# CH32V303RBT6-R1.net
KiCad netlist of a schematic drawn in Altium Designer
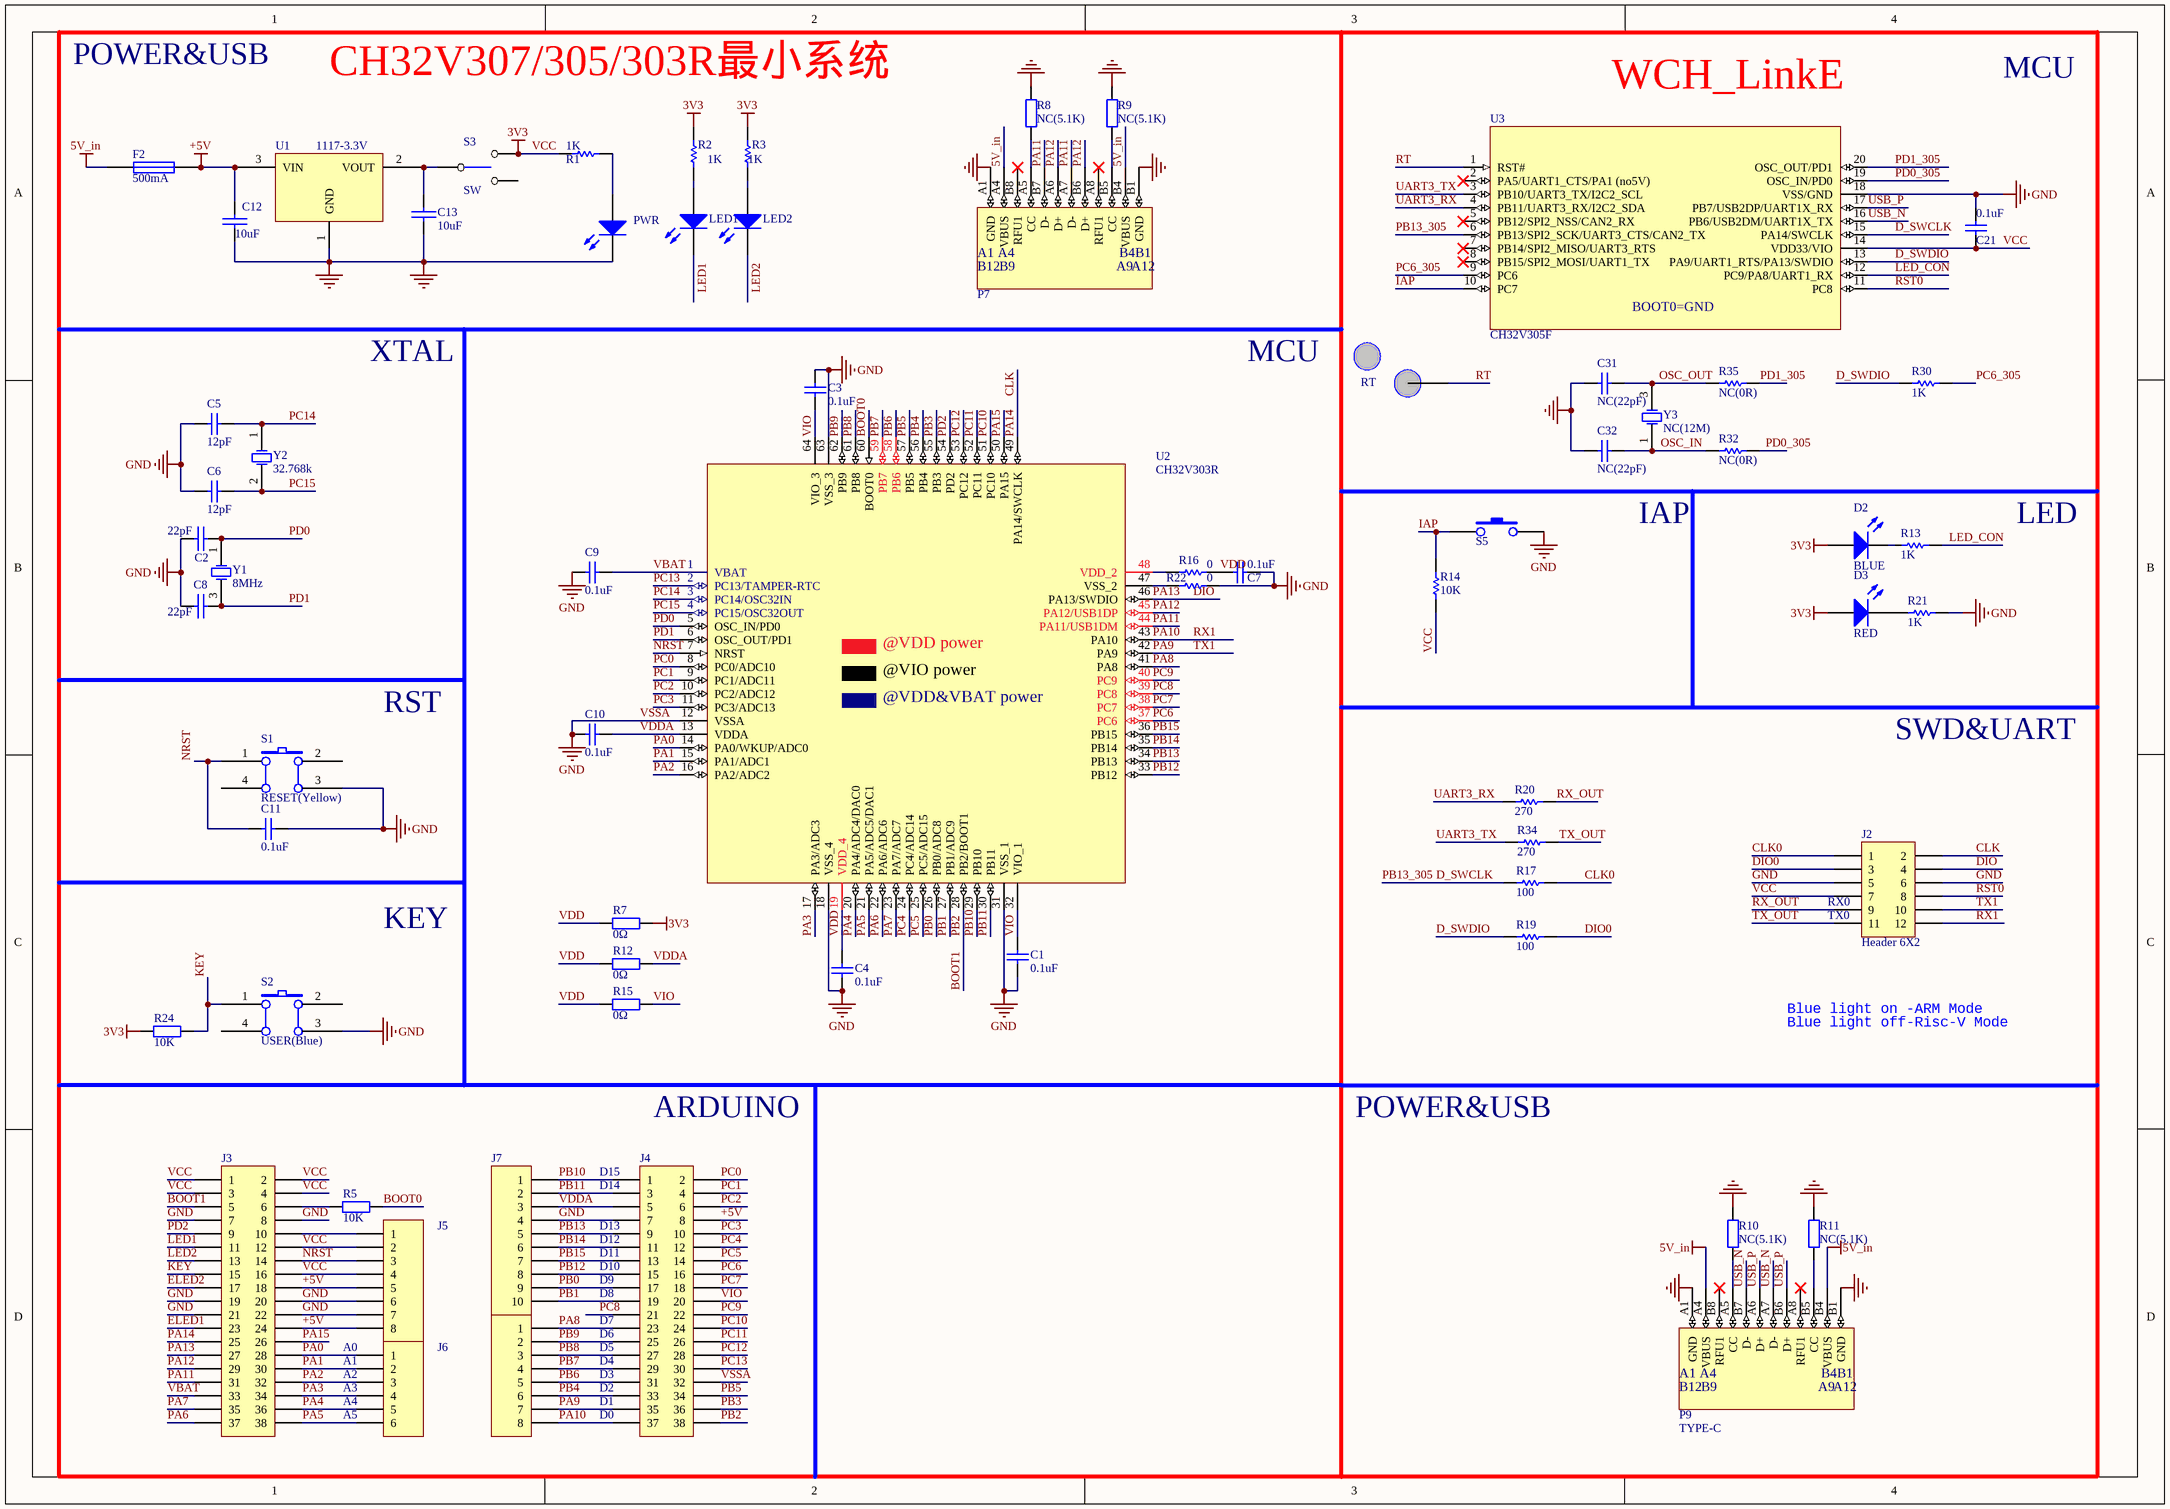
[diagram p0: CH32V303RBT6-R1.SchDoc]

(export (version "E")
  (design (tool "Eeschema 10.0.6"))
  (components
    (comp (ref "C1")
      (value "0.1uF")
      (footprint "0603_C")
      (description "Capacitor")
      (libsource (lib "Miscellaneous Devices") (part "Cap"))
    )
    (comp (ref "C2")
      (value "22pF")
      (footprint "0603_C")
      (description "Capacitor")
      (libsource (lib "*") (part "CAP"))
    )
    (comp (ref "C3")
      (value "0.1uF")
      (footprint "0603_C")
      (description "Capacitor")
      (libsource (lib "Miscellaneous Devices") (part "Cap"))
    )
    (comp (ref "C4")
      (value "0.1uF")
      (footprint "0603_C")
      (description "Capacitor")
      (libsource (lib "Miscellaneous Devices") (part "Cap"))
    )
    (comp (ref "C5")
      (value "12pF")
      (footprint "0603_C")
      (description "Capacitor")
      (libsource (lib "Miscellaneous Devices") (part "Cap"))
    )
    (comp (ref "C6")
      (value "12pF")
      (footprint "0603_C")
      (description "Capacitor")
      (libsource (lib "Miscellaneous Devices") (part "Cap"))
    )
    (comp (ref "C7")
      (value "0.1uF")
      (footprint "0603_C")
      (description "Capacitor")
      (libsource (lib "Miscellaneous Devices") (part "Cap"))
    )
    (comp (ref "C8")
      (value "22pF")
      (footprint "0603_C")
      (description "Capacitor")
      (libsource (lib "*") (part "CAP"))
    )
    (comp (ref "C9")
      (value "0.1uF")
      (footprint "0603_C")
      (description "Capacitor")
      (libsource (lib "Miscellaneous Devices") (part "Cap"))
    )
    (comp (ref "C10")
      (value "0.1uF")
      (footprint "0603_C")
      (description "Capacitor")
      (libsource (lib "Miscellaneous Devices") (part "Cap"))
    )
    (comp (ref "C11")
      (value "0.1uF")
      (footprint "0603_C")
      (description "Capacitor")
      (libsource (lib "Miscellaneous Devices") (part "Cap"))
    )
    (comp (ref "C12")
      (value "10uF")
      (footprint "3216_C")
      (description "Capacitor")
      (libsource (lib "*") (part "CAP"))
    )
    (comp (ref "C13")
      (value "10uF")
      (footprint "3216_C")
      (description "Capacitor")
      (libsource (lib "*") (part "CAP"))
    )
    (comp (ref "C21")
      (value "0.1uF")
      (footprint "0603_C")
      (description "Capacitor")
      (libsource (lib "Miscellaneous Devices") (part "Cap"))
    )
    (comp (ref "C31")
      (value "NC(22pF)")
      (footprint "0603_C")
      (description "Capacitor")
      (fields (field (name "PUBLISHER") "Altium Limited"))
      (libsource (lib "*") (part "Cap"))
    )
    (comp (ref "C32")
      (value "NC(22pF)")
      (footprint "0603_C")
      (description "Capacitor")
      (fields (field (name "PUBLISHER") "Altium Limited"))
      (libsource (lib "*") (part "Cap"))
    )
    (comp (ref "D2")
      (value "BLUE")
      (footprint "0603+")
      (description "Typical RED, GREEN, YELLOW, AMBER GaAs LED")
      (fields (field (name "PUBLISHER") "Altium Limited"))
      (libsource (lib "MYLIB") (part "D0603"))
    )
    (comp (ref "D3")
      (value "RED")
      (footprint "0603+")
      (description "Typical RED, GREEN, YELLOW, AMBER GaAs LED")
      (fields (field (name "PUBLISHER") "Altium Limited"))
      (libsource (lib "MYLIB") (part "D0603"))
    )
    (comp (ref "F2")
      (value "500mA")
      (footprint "0805")
      (description "Fuse")
      (libsource (lib "*") (part "FUSE1"))
    )
    (comp (ref "J2")
      (value "Header 6X2")
      (footprint "IDC12-2.54mm")
      (description "Header, 6-Pin, Dual row")
      (fields (field (name "PUBLISHER") "Altium Limited"))
      (libsource (lib "Miscellaneous Connectors") (part "Header 6X2"))
    )
    (comp (ref "J3")
      (value "Header 19X2")
      (footprint "IDC38-2.54mm")
      (description "Header, 19-Pin, Dual row")
      (fields (field (name "PUBLISHER") "Altium Limited"))
      (libsource (lib "Miscellaneous Connectors") (part "Header 19X2"))
    )
    (comp (ref "J4")
      (value "Header 19X2")
      (footprint "IDC38-2.54mm")
      (description "Header, 19-Pin, Dual row")
      (fields (field (name "PUBLISHER") "Altium Limited"))
      (libsource (lib "Miscellaneous Connectors") (part "Header 19X2"))
    )
    (comp (ref "J5")
      (value "Header 8")
      (footprint "SIP8-2.54mm")
      (description "Header, 8-Pin")
      (fields (field (name "PUBLISHER") "Altium Limited"))
      (libsource (lib "") (part "Header 8_1"))
    )
    (comp (ref "J6")
      (value "Header 6")
      (footprint "SIP6-2.54MM")
      (description "Header, 6-Pin")
      (fields (field (name "PUBLISHER") "Altium Limited"))
      (libsource (lib "Miscellaneous Connectors") (part "Header 6"))
    )
    (comp (ref "J7")
      (value "Header 10")
      (footprint "SIP10-2.54mm")
      (description "Header, 10-Pin")
      (fields (field (name "PUBLISHER") "Altium Limited"))
      (libsource (lib "Miscellaneous Connectors") (part "Header 10"))
    )
    (comp (ref "J8")
      (value "Header 8")
      (footprint "SIP8-2.54mm")
      (description "Header, 8-Pin")
      (fields (field (name "PUBLISHER") "Altium Limited"))
      (libsource (lib "Miscellaneous Connectors") (part "Header 8"))
    )
    (comp (ref "LED1")
      (value "LED1   blue")
      (footprint "0603+")
      (description "Typical INFRARED GaAs LED")
      (fields (field (name "PUBLISHER") "Altium Limited"))
      (libsource (lib "Miscellaneous Devices") (part "LED0"))
    )
    (comp (ref "LED2")
      (value "LED2  blue")
      (footprint "0603+")
      (description "Typical INFRARED GaAs LED")
      (fields (field (name "PUBLISHER") "Altium Limited"))
      (libsource (lib "Miscellaneous Devices") (part "LED0"))
    )
    (comp (ref "P7")
      (value "TYPE-C")
      (footprint "TYPE-C-Receptacle-2.0")
      (libsource (lib "*") (part "TYPE-C1"))
    )
    (comp (ref "P9")
      (value "TYPE-C")
      (footprint "TYPE-C-Receptacle-2.0")
      (libsource (lib "*") (part "TYPE-C1"))
    )
    (comp (ref "PWR")
      (value "POWER  red")
      (footprint "0603+")
      (description "Typical INFRARED GaAs LED")
      (fields (field (name "PUBLISHER") "Altium Limited"))
      (libsource (lib "Miscellaneous Devices") (part "LED0"))
    )
    (comp (ref "R1")
      (value "1K")
      (footprint "0603")
      (description "Semiconductor Resistor")
      (libsource (lib "Miscellaneous Devices") (part "Res Semi"))
    )
    (comp (ref "R2")
      (value "1K")
      (footprint "0603")
      (description "Semiconductor Resistor")
      (libsource (lib "Miscellaneous Devices") (part "Res Semi"))
    )
    (comp (ref "R3")
      (value "1K")
      (footprint "0603")
      (description "Semiconductor Resistor")
      (libsource (lib "Miscellaneous Devices") (part "Res Semi"))
    )
    (comp (ref "R5")
      (value "10K")
      (footprint "0603")
      (description "Resistor")
      (libsource (lib "") (part "Res2_1"))
    )
    (comp (ref "R7")
      (value "0Ω")
      (footprint "0603")
      (description "Resistor")
      (libsource (lib "Miscellaneous Devices") (part "Res2"))
    )
    (comp (ref "R8")
      (value "NC(5.1K)")
      (footprint "0603")
      (description "Resistor")
      (libsource (lib "") (part "Res2_3"))
    )
    (comp (ref "R9")
      (value "NC(5.1K)")
      (footprint "0603")
      (description "Resistor")
      (libsource (lib "") (part "Res2_3"))
    )
    (comp (ref "R10")
      (value "NC(5.1K)")
      (footprint "0603")
      (description "Resistor")
      (libsource (lib "") (part "Res2_2"))
    )
    (comp (ref "R11")
      (value "NC(5.1K)")
      (footprint "0603")
      (description "Resistor")
      (libsource (lib "") (part "Res2_2"))
    )
    (comp (ref "R12")
      (value "0Ω")
      (footprint "0603")
      (description "Resistor")
      (libsource (lib "Miscellaneous Devices") (part "Res2"))
    )
    (comp (ref "R13")
      (value "1K")
      (footprint "0603")
      (description "Resistor")
      (fields (field (name "PUBLISHER") "Altium Limited"))
      (libsource (lib "MYLIB") (part "0603-1"))
    )
    (comp (ref "R14")
      (value "10K")
      (footprint "0603")
      (description "Resistor")
      (fields (field (name "PUBLISHER") "Altium Limited"))
      (libsource (lib "MYLIB") (part "0603-1"))
    )
    (comp (ref "R15")
      (value "0Ω")
      (footprint "0603")
      (description "Resistor")
      (libsource (lib "Miscellaneous Devices") (part "Res2"))
    )
    (comp (ref "R16")
      (value "0")
      (footprint "0603")
      (description "Resistor")
      (fields (field (name "PUBLISHER") "Altium Limited"))
      (libsource (lib "MYLIB") (part "0603-1"))
    )
    (comp (ref "R17")
      (value "100")
      (footprint "0603")
      (description "Resistor")
      (fields (field (name "PUBLISHER") "Altium Limited"))
      (libsource (lib "MYLIB") (part "0603-1"))
    )
    (comp (ref "R19")
      (value "100")
      (footprint "0603")
      (description "Resistor")
      (fields (field (name "PUBLISHER") "Altium Limited"))
      (libsource (lib "MYLIB") (part "0603-1"))
    )
    (comp (ref "R20")
      (value "270")
      (footprint "0603")
      (description "Resistor")
      (fields (field (name "PUBLISHER") "Altium Limited"))
      (libsource (lib "MYLIB") (part "0603-1"))
    )
    (comp (ref "R21")
      (value "1K")
      (footprint "0603")
      (description "Resistor")
      (fields (field (name "PUBLISHER") "Altium Limited"))
      (libsource (lib "MYLIB") (part "0603-1"))
    )
    (comp (ref "R22")
      (value "0")
      (footprint "0603")
      (description "Resistor")
      (fields (field (name "PUBLISHER") "Altium Limited"))
      (libsource (lib "MYLIB") (part "0603-1"))
    )
    (comp (ref "R24")
      (value "10K")
      (footprint "0603")
      (description "Resistor")
      (libsource (lib "Miscellaneous Devices") (part "Res2"))
    )
    (comp (ref "R30")
      (value "1K")
      (footprint "0603")
      (description "Resistor")
      (fields (field (name "PUBLISHER") "Altium Limited"))
      (libsource (lib "MYLIB") (part "0603-1"))
    )
    (comp (ref "R32")
      (value "NC(0R)")
      (footprint "0603")
      (description "Resistor")
      (fields (field (name "PUBLISHER") "Altium Limited"))
      (libsource (lib "MYLIB") (part "0603-1"))
    )
    (comp (ref "R34")
      (value "270")
      (footprint "0603")
      (description "Resistor")
      (fields (field (name "PUBLISHER") "Altium Limited"))
      (libsource (lib "MYLIB") (part "0603-1"))
    )
    (comp (ref "R35")
      (value "NC(0R)")
      (footprint "0603")
      (description "Resistor")
      (fields (field (name "PUBLISHER") "Altium Limited"))
      (libsource (lib "MYLIB") (part "0603-1"))
    )
    (comp (ref "RT")
      (value "Testpoint")
      (footprint "TESTPOINT1")
      (description "测试点")
      (libsource (lib "wch_sch_others") (part "Testpoint"))
    )
    (comp (ref "S1")
      (value "RESET(Yellow)")
      (footprint "KEYX")
      (description "SE PUSHBUTTON")
      (libsource (lib "Documents") (part "SW PUSHBUTTON"))
    )
    (comp (ref "S2")
      (value "USER(Blue)")
      (footprint "KEYX")
      (description "SE PUSHBUTTON")
      (libsource (lib "Documents") (part "SW PUSHBUTTON"))
    )
    (comp (ref "S3") (value "SW") (footprint "SW1") (libsource (lib "MYSCH") (part "SW")))
    (comp (ref "S5") (value "KEY") (footprint "贴片按键") (libsource (lib "*") (part "KEY")))
    (comp (ref "U1")
      (value "1117-3.3V")
      (footprint "SOT-223")
      (libsource (lib "wch_sch_others") (part "1117-3.3V"))
    )
    (comp (ref "U2")
      (value "CH32V303R")
      (footprint "LQFP64M_10x10")
      (description "RISC-V FPU HD-MCU, 144MHz, 8*UART, 10*Timer, 4*OPA")
      (libsource (lib "CHXXX") (part "CH32V303R"))
    )
    (comp (ref "U3")
      (value "CH32V305F")
      (footprint "TSSOP20")
      (description "RISC-V FPU HD-MCU, 144MHz, USB_480M, CAN, UART*2, SPI")
      (libsource (lib "CHXXX") (part "CH32V305F"))
    )
    (comp (ref "Y1")
      (value "8MHz")
      (footprint "XT3225")
      (description "Crystal Oscillator")
      (fields (field (name "PUBLISHER") "Altium Limited"))
      (libsource (lib "*") (part "XTAL"))
    )
    (comp (ref "Y2")
      (value "32.768k")
      (footprint "FC-135")
      (description "Crystal Oscillator")
      (fields (field (name "PUBLISHER") "Altium Limited"))
      (libsource (lib "Miscellaneous Devices") (part "XTAL"))
    )
    (comp (ref "Y3")
      (value "NC(12M)")
      (footprint "XT3225")
      (description "Crystal Oscillator")
      (libsource (lib "*") (part "XTAL"))
    )
  )
  (nets
    (net (code "1") (name "+5V") (class "Default")
      (node (ref "C12") (pin "1") (pinfunction "1_1") (pintype "passive"))
      (node (ref "F2") (pin "2") (pinfunction "2_2") (pintype "passive"))
      (node (ref "J3") (pin "18") (pinfunction "18_18") (pintype "passive"))
      (node (ref "J3") (pin "24") (pinfunction "24_24") (pintype "passive"))
      (node (ref "J4") (pin "8") (pinfunction "8_8") (pintype "passive"))
      (node (ref "J5") (pin "5") (pinfunction "5_5") (pintype "passive"))
      (node (ref "J5") (pin "8") (pinfunction "8_8") (pintype "passive"))
      (node (ref "U1") (pin "3") (pinfunction "VIN_3") (pintype "passive"))
    )
    (net (code "2") (name "/BOOT0") (class "Default")
      (node (ref "R5") (pin "2") (pinfunction "2_2") (pintype "passive"))
      (node (ref "U2") (pin "60") (pinfunction "BOOT0_60") (pintype "input"))
    )
    (net (code "3") (name "/BOOT1") (class "Default")
      (node (ref "J3") (pin "5") (pinfunction "5_5") (pintype "passive"))
      (node (ref "J4") (pin "38") (pinfunction "38_38") (pintype "passive"))
      (node (ref "U2") (pin "28") (pinfunction "PB2/BOOT1_28") (pintype "bidirectional"))
    )
    (net (code "4") (name "/CLK") (class "Default")
      (node (ref "J2") (pin "2") (pinfunction "2_2") (pintype "passive"))
      (node (ref "J3") (pin "25") (pinfunction "25_25") (pintype "passive"))
      (node (ref "U2") (pin "49") (pinfunction "PA14/SWCLK_49") (pintype "bidirectional"))
    )
    (net (code "5") (name "/CLK0") (class "Default")
      (node (ref "J2") (pin "1") (pinfunction "1_1") (pintype "passive"))
      (node (ref "R17") (pin "1") (pinfunction "1_1") (pintype "passive"))
    )
    (net (code "6") (name "/DIO") (class "Default")
      (node (ref "J2") (pin "4") (pinfunction "4_4") (pintype "passive"))
      (node (ref "J3") (pin "27") (pinfunction "27_27") (pintype "passive"))
      (node (ref "U2") (pin "46") (pinfunction "PA13/SWDIO_46") (pintype "bidirectional"))
    )
    (net (code "7") (name "/DIO0") (class "Default")
      (node (ref "J2") (pin "3") (pinfunction "3_3") (pintype "passive"))
      (node (ref "R19") (pin "1") (pinfunction "1_1") (pintype "passive"))
    )
    (net (code "8") (name "/D_SWCLK") (class "Default")
      (node (ref "R17") (pin "2") (pinfunction "2_2") (pintype "passive"))
      (node (ref "U3") (pin "15") (pinfunction "PA14/SWCLK_15") (pintype "bidirectional"))
      (node (ref "U3") (pin "6") (pinfunction "PB13/SPI2_SCK/UART3_CTS/CAN2_TX_6") (pintype "bidirectional"))
    )
    (net (code "9") (name "/D_SWDIO") (class "Default")
      (node (ref "R19") (pin "2") (pinfunction "2_2") (pintype "passive"))
      (node (ref "R30") (pin "1") (pinfunction "1_1") (pintype "passive"))
      (node (ref "U3") (pin "13") (pinfunction "PA9/UART1_RTS/PA13/SWDIO_13") (pintype "bidirectional"))
    )
    (net (code "10") (name "/ELED1") (class "Default")
      (node (ref "J3") (pin "23") (pinfunction "23_23") (pintype "passive"))
    )
    (net (code "11") (name "/ELED2") (class "Default")
      (node (ref "J3") (pin "17") (pinfunction "17_17") (pintype "passive"))
    )
    (net (code "12") (name "/IAP") (class "Default")
      (node (ref "R14") (pin "1") (pinfunction "1_1") (pintype "passive"))
      (node (ref "S5") (pin "1") (pinfunction "1_1") (pintype "passive"))
      (node (ref "U3") (pin "10") (pinfunction "PC7_10") (pintype "bidirectional"))
    )
    (net (code "13") (name "/KEY") (class "Default")
      (node (ref "J3") (pin "15") (pinfunction "15_15") (pintype "passive"))
      (node (ref "R24") (pin "1") (pinfunction "1_1") (pintype "passive"))
      (node (ref "S2") (pin "1") (pinfunction "A0_1") (pintype "passive"))
    )
    (net (code "14") (name "/LED1") (class "Default")
      (node (ref "J3") (pin "11") (pinfunction "11_11") (pintype "passive"))
      (node (ref "LED1") (pin "2") (pinfunction "K_2") (pintype "passive"))
    )
    (net (code "15") (name "/LED2") (class "Default")
      (node (ref "J3") (pin "13") (pinfunction "13_13") (pintype "passive"))
      (node (ref "LED2") (pin "2") (pinfunction "K_2") (pintype "passive"))
    )
    (net (code "16") (name "/LED_CON") (class "Default")
      (node (ref "R13") (pin "1") (pinfunction "1_1") (pintype "passive"))
      (node (ref "U3") (pin "12") (pinfunction "PC9/PA8/UART1_RX_12") (pintype "bidirectional"))
    )
    (net (code "17") (name "/NRST") (class "Default")
      (node (ref "C11") (pin "2") (pinfunction "2_2") (pintype "passive"))
      (node (ref "J3") (pin "14") (pinfunction "14_14") (pintype "passive"))
      (node (ref "J5") (pin "3") (pinfunction "3_3") (pintype "passive"))
      (node (ref "S1") (pin "1") (pinfunction "A0_1") (pintype "passive"))
      (node (ref "U2") (pin "7") (pinfunction "NRST_7") (pintype "input"))
    )
    (net (code "18") (name "/OSC_IN") (class "Default")
      (node (ref "C32") (pin "2") (pinfunction "2_2") (pintype "passive"))
      (node (ref "R32") (pin "2") (pinfunction "2_2") (pintype "passive"))
      (node (ref "Y3") (pin "1") (pinfunction "OSC1_1") (pintype "passive"))
    )
    (net (code "19") (name "/OSC_OUT") (class "Default")
      (node (ref "C31") (pin "2") (pinfunction "2_2") (pintype "passive"))
      (node (ref "R35") (pin "2") (pinfunction "2_2") (pintype "passive"))
      (node (ref "Y3") (pin "3") (pinfunction "OSC2_3") (pintype "passive"))
    )
    (net (code "20") (name "/PA0") (class "Default")
      (node (ref "J3") (pin "28") (pinfunction "28_28") (pintype "passive"))
      (node (ref "J6") (pin "1") (pinfunction "1_1") (pintype "passive"))
      (node (ref "U2") (pin "14") (pinfunction "PA0/WKUP/ADC0_14") (pintype "bidirectional"))
    )
    (net (code "21") (name "/PA1") (class "Default")
      (node (ref "J3") (pin "30") (pinfunction "30_30") (pintype "passive"))
      (node (ref "J6") (pin "2") (pinfunction "2_2") (pintype "passive"))
      (node (ref "U2") (pin "15") (pinfunction "PA1/ADC1_15") (pintype "bidirectional"))
    )
    (net (code "22") (name "/PA2") (class "Default")
      (node (ref "J3") (pin "32") (pinfunction "32_32") (pintype "passive"))
      (node (ref "J6") (pin "3") (pinfunction "3_3") (pintype "passive"))
      (node (ref "U2") (pin "16") (pinfunction "PA2/ADC2_16") (pintype "bidirectional"))
    )
    (net (code "23") (name "/PA3") (class "Default")
      (node (ref "J3") (pin "34") (pinfunction "34_34") (pintype "passive"))
      (node (ref "J6") (pin "4") (pinfunction "4_4") (pintype "passive"))
      (node (ref "U2") (pin "17") (pinfunction "PA3/ADC3_17") (pintype "bidirectional"))
    )
    (net (code "24") (name "/PA4") (class "Default")
      (node (ref "J3") (pin "36") (pinfunction "36_36") (pintype "passive"))
      (node (ref "J6") (pin "5") (pinfunction "5_5") (pintype "passive"))
      (node (ref "U2") (pin "20") (pinfunction "PA4/ADC4/DAC0_20") (pintype "bidirectional"))
    )
    (net (code "25") (name "/PA5") (class "Default")
      (node (ref "J3") (pin "38") (pinfunction "38_38") (pintype "passive"))
      (node (ref "J6") (pin "6") (pinfunction "6_6") (pintype "passive"))
      (node (ref "U2") (pin "21") (pinfunction "PA5/ADC5/DAC1_21") (pintype "bidirectional"))
    )
    (net (code "26") (name "/PA6") (class "Default")
      (node (ref "J3") (pin "37") (pinfunction "37_37") (pintype "passive"))
      (node (ref "U2") (pin "22") (pinfunction "PA6/ADC6_22") (pintype "bidirectional"))
    )
    (net (code "27") (name "/PA7") (class "Default")
      (node (ref "J3") (pin "35") (pinfunction "35_35") (pintype "passive"))
      (node (ref "U2") (pin "23") (pinfunction "PA7/ADC7_23") (pintype "bidirectional"))
    )
    (net (code "28") (name "/PA8") (class "Default")
      (node (ref "J4") (pin "23") (pinfunction "23_23") (pintype "passive"))
      (node (ref "J8") (pin "1") (pinfunction "1_1") (pintype "passive"))
      (node (ref "U2") (pin "41") (pinfunction "PA8_41") (pintype "bidirectional"))
    )
    (net (code "29") (name "/PA9") (class "Default")
      (node (ref "J2") (pin "10") (pinfunction "10_10") (pintype "passive"))
      (node (ref "J4") (pin "35") (pinfunction "35_35") (pintype "passive"))
      (node (ref "J8") (pin "7") (pinfunction "7_7") (pintype "passive"))
      (node (ref "U2") (pin "42") (pinfunction "PA9_42") (pintype "bidirectional"))
    )
    (net (code "30") (name "/PA10") (class "Default")
      (node (ref "J2") (pin "12") (pinfunction "12_12") (pintype "passive"))
      (node (ref "J4") (pin "37") (pinfunction "37_37") (pintype "passive"))
      (node (ref "J8") (pin "8") (pinfunction "8_8") (pintype "passive"))
      (node (ref "U2") (pin "43") (pinfunction "PA10_43") (pintype "bidirectional"))
    )
    (net (code "31") (name "/PA11") (class "Default")
      (node (ref "J3") (pin "31") (pinfunction "31_31") (pintype "passive"))
      (node (ref "P7") (pin "A7") (pinfunction "D-_A7") (pintype "bidirectional"))
      (node (ref "P7") (pin "B7") (pinfunction "D-_B7") (pintype "bidirectional"))
      (node (ref "U2") (pin "44") (pinfunction "PA11/USB1DM_44") (pintype "bidirectional"))
    )
    (net (code "32") (name "/PA12") (class "Default")
      (node (ref "J3") (pin "29") (pinfunction "29_29") (pintype "passive"))
      (node (ref "P7") (pin "A6") (pinfunction "D+_A6") (pintype "bidirectional"))
      (node (ref "P7") (pin "B6") (pinfunction "D+_B6") (pintype "bidirectional"))
      (node (ref "U2") (pin "45") (pinfunction "PA12/USB1DP_45") (pintype "bidirectional"))
    )
    (net (code "33") (name "/PA15") (class "Default")
      (node (ref "J3") (pin "26") (pinfunction "26_26") (pintype "passive"))
      (node (ref "U2") (pin "50") (pinfunction "PA15_50") (pintype "bidirectional"))
    )
    (net (code "34") (name "/PB0") (class "Default")
      (node (ref "J4") (pin "17") (pinfunction "17_17") (pintype "passive"))
      (node (ref "J7") (pin "9") (pinfunction "9_9") (pintype "passive"))
      (node (ref "U2") (pin "26") (pinfunction "PB0/ADC8_26") (pintype "bidirectional"))
    )
    (net (code "35") (name "/PB1") (class "Default")
      (node (ref "J4") (pin "19") (pinfunction "19_19") (pintype "passive"))
      (node (ref "J7") (pin "10") (pinfunction "10_10") (pintype "passive"))
      (node (ref "U2") (pin "27") (pinfunction "PB1/ADC9_27") (pintype "bidirectional"))
    )
    (net (code "36") (name "/PB3") (class "Default")
      (node (ref "J4") (pin "36") (pinfunction "36_36") (pintype "passive"))
      (node (ref "U2") (pin "55") (pinfunction "PB3_55") (pintype "bidirectional"))
    )
    (net (code "37") (name "/PB4") (class "Default")
      (node (ref "J4") (pin "33") (pinfunction "33_33") (pintype "passive"))
      (node (ref "J8") (pin "6") (pinfunction "6_6") (pintype "passive"))
      (node (ref "U2") (pin "56") (pinfunction "PB4_56") (pintype "bidirectional"))
    )
    (net (code "38") (name "/PB5") (class "Default")
      (node (ref "J4") (pin "34") (pinfunction "34_34") (pintype "passive"))
      (node (ref "U2") (pin "57") (pinfunction "PB5_57") (pintype "bidirectional"))
    )
    (net (code "39") (name "/PB6") (class "Default")
      (node (ref "J4") (pin "31") (pinfunction "31_31") (pintype "passive"))
      (node (ref "J8") (pin "5") (pinfunction "5_5") (pintype "passive"))
      (node (ref "U2") (pin "58") (pinfunction "PB6_58") (pintype "bidirectional"))
    )
    (net (code "40") (name "/PB7") (class "Default")
      (node (ref "J4") (pin "29") (pinfunction "29_29") (pintype "passive"))
      (node (ref "J8") (pin "4") (pinfunction "4_4") (pintype "passive"))
      (node (ref "U2") (pin "59") (pinfunction "PB7_59") (pintype "bidirectional"))
    )
    (net (code "41") (name "/PB8") (class "Default")
      (node (ref "J4") (pin "27") (pinfunction "27_27") (pintype "passive"))
      (node (ref "J8") (pin "3") (pinfunction "3_3") (pintype "passive"))
      (node (ref "U2") (pin "61") (pinfunction "PB8_61") (pintype "bidirectional"))
    )
    (net (code "42") (name "/PB9") (class "Default")
      (node (ref "J4") (pin "25") (pinfunction "25_25") (pintype "passive"))
      (node (ref "J8") (pin "2") (pinfunction "2_2") (pintype "passive"))
      (node (ref "U2") (pin "62") (pinfunction "PB9_62") (pintype "bidirectional"))
    )
    (net (code "43") (name "/PB10") (class "Default")
      (node (ref "J4") (pin "1") (pinfunction "1_1") (pintype "passive"))
      (node (ref "J7") (pin "1") (pinfunction "1_1") (pintype "passive"))
      (node (ref "U2") (pin "29") (pinfunction "PB10_29") (pintype "bidirectional"))
    )
    (net (code "44") (name "/PB11") (class "Default")
      (node (ref "J4") (pin "3") (pinfunction "3_3") (pintype "passive"))
      (node (ref "J7") (pin "2") (pinfunction "2_2") (pintype "passive"))
      (node (ref "U2") (pin "30") (pinfunction "PB11_30") (pintype "bidirectional"))
    )
    (net (code "45") (name "/PB12") (class "Default")
      (node (ref "J4") (pin "15") (pinfunction "15_15") (pintype "passive"))
      (node (ref "J7") (pin "8") (pinfunction "8_8") (pintype "passive"))
      (node (ref "U2") (pin "33") (pinfunction "PB12_33") (pintype "bidirectional"))
    )
    (net (code "46") (name "/PB13") (class "Default")
      (node (ref "J4") (pin "9") (pinfunction "9_9") (pintype "passive"))
      (node (ref "J7") (pin "5") (pinfunction "5_5") (pintype "passive"))
      (node (ref "U2") (pin "34") (pinfunction "PB13_34") (pintype "bidirectional"))
    )
    (net (code "47") (name "/PB14") (class "Default")
      (node (ref "J4") (pin "11") (pinfunction "11_11") (pintype "passive"))
      (node (ref "J7") (pin "6") (pinfunction "6_6") (pintype "passive"))
      (node (ref "U2") (pin "35") (pinfunction "PB14_35") (pintype "bidirectional"))
    )
    (net (code "48") (name "/PB15") (class "Default")
      (node (ref "J4") (pin "13") (pinfunction "13_13") (pintype "passive"))
      (node (ref "J7") (pin "7") (pinfunction "7_7") (pintype "passive"))
      (node (ref "U2") (pin "36") (pinfunction "PB15_36") (pintype "bidirectional"))
    )
    (net (code "49") (name "/PC0") (class "Default")
      (node (ref "J4") (pin "2") (pinfunction "2_2") (pintype "passive"))
      (node (ref "U2") (pin "8") (pinfunction "PC0/ADC10_8") (pintype "bidirectional"))
    )
    (net (code "50") (name "/PC1") (class "Default")
      (node (ref "J4") (pin "4") (pinfunction "4_4") (pintype "passive"))
      (node (ref "U2") (pin "9") (pinfunction "PC1/ADC11_9") (pintype "bidirectional"))
    )
    (net (code "51") (name "/PC2") (class "Default")
      (node (ref "J4") (pin "6") (pinfunction "6_6") (pintype "passive"))
      (node (ref "U2") (pin "10") (pinfunction "PC2/ADC12_10") (pintype "bidirectional"))
    )
    (net (code "52") (name "/PC3") (class "Default")
      (node (ref "J4") (pin "10") (pinfunction "10_10") (pintype "passive"))
      (node (ref "U2") (pin "11") (pinfunction "PC3/ADC13_11") (pintype "bidirectional"))
    )
    (net (code "53") (name "/PC4") (class "Default")
      (node (ref "J4") (pin "12") (pinfunction "12_12") (pintype "passive"))
      (node (ref "U2") (pin "24") (pinfunction "PC4/ADC14_24") (pintype "bidirectional"))
    )
    (net (code "54") (name "/PC5") (class "Default")
      (node (ref "J4") (pin "14") (pinfunction "14_14") (pintype "passive"))
      (node (ref "U2") (pin "25") (pinfunction "PC5/ADC15_25") (pintype "bidirectional"))
    )
    (net (code "55") (name "/PC6") (class "Default")
      (node (ref "J4") (pin "16") (pinfunction "16_16") (pintype "passive"))
      (node (ref "U2") (pin "37") (pinfunction "PC6_37") (pintype "bidirectional"))
    )
    (net (code "56") (name "/PC6_305") (class "Default")
      (node (ref "R30") (pin "2") (pinfunction "2_2") (pintype "passive"))
      (node (ref "U3") (pin "9") (pinfunction "PC6_9") (pintype "bidirectional"))
    )
    (net (code "57") (name "/PC7") (class "Default")
      (node (ref "J4") (pin "18") (pinfunction "18_18") (pintype "passive"))
      (node (ref "U2") (pin "38") (pinfunction "PC7_38") (pintype "bidirectional"))
    )
    (net (code "58") (name "/PC8") (class "Default")
      (node (ref "J4") (pin "21") (pinfunction "21_21") (pintype "passive"))
      (node (ref "U2") (pin "39") (pinfunction "PC8_39") (pintype "bidirectional"))
    )
    (net (code "59") (name "/PC9") (class "Default")
      (node (ref "J4") (pin "22") (pinfunction "22_22") (pintype "passive"))
      (node (ref "U2") (pin "40") (pinfunction "PC9_40") (pintype "bidirectional"))
    )
    (net (code "60") (name "/PC10") (class "Default")
      (node (ref "J4") (pin "24") (pinfunction "24_24") (pintype "passive"))
      (node (ref "U2") (pin "51") (pinfunction "PC10_51") (pintype "bidirectional"))
    )
    (net (code "61") (name "/PC11") (class "Default")
      (node (ref "J4") (pin "26") (pinfunction "26_26") (pintype "passive"))
      (node (ref "U2") (pin "52") (pinfunction "PC11_52") (pintype "bidirectional"))
    )
    (net (code "62") (name "/PC12") (class "Default")
      (node (ref "J4") (pin "28") (pinfunction "28_28") (pintype "passive"))
      (node (ref "U2") (pin "53") (pinfunction "PC12_53") (pintype "bidirectional"))
    )
    (net (code "63") (name "/PC13") (class "Default")
      (node (ref "J4") (pin "30") (pinfunction "30_30") (pintype "passive"))
      (node (ref "U2") (pin "2") (pinfunction "PC13/TAMPER-RTC_2") (pintype "bidirectional"))
    )
    (net (code "64") (name "/PC14") (class "Default")
      (node (ref "C5") (pin "1") (pinfunction "1_1") (pintype "passive"))
      (node (ref "U2") (pin "3") (pinfunction "PC14/OSC32IN_3") (pintype "bidirectional"))
      (node (ref "Y2") (pin "1") (pinfunction "OSC1_1") (pintype "passive"))
    )
    (net (code "65") (name "/PC15") (class "Default")
      (node (ref "C6") (pin "1") (pinfunction "1_1") (pintype "passive"))
      (node (ref "U2") (pin "4") (pinfunction "PC15/OSC32OUT_4") (pintype "bidirectional"))
      (node (ref "Y2") (pin "2") (pinfunction "OSC2_2") (pintype "passive"))
    )
    (net (code "66") (name "/PD0") (class "Default")
      (node (ref "C2") (pin "2") (pinfunction "2_2") (pintype "passive"))
      (node (ref "U2") (pin "5") (pinfunction "OSC_IN/PD0_5") (pintype "bidirectional"))
      (node (ref "Y1") (pin "1") (pinfunction "OSC1_1") (pintype "passive"))
    )
    (net (code "67") (name "/PD0_305") (class "Default")
      (node (ref "R32") (pin "1") (pinfunction "1_1") (pintype "passive"))
      (node (ref "U3") (pin "19") (pinfunction "OSC_IN/PD0_19") (pintype "bidirectional"))
    )
    (net (code "68") (name "/PD1") (class "Default")
      (node (ref "C8") (pin "2") (pinfunction "2_2") (pintype "passive"))
      (node (ref "U2") (pin "6") (pinfunction "OSC_OUT/PD1_6") (pintype "bidirectional"))
      (node (ref "Y1") (pin "3") (pinfunction "OSC2_3") (pintype "passive"))
    )
    (net (code "69") (name "/PD1_305") (class "Default")
      (node (ref "R35") (pin "1") (pinfunction "1_1") (pintype "passive"))
      (node (ref "U3") (pin "20") (pinfunction "OSC_OUT/PD1_20") (pintype "bidirectional"))
    )
    (net (code "70") (name "/PD2") (class "Default")
      (node (ref "J3") (pin "9") (pinfunction "9_9") (pintype "passive"))
      (node (ref "U2") (pin "54") (pinfunction "PD2_54") (pintype "bidirectional"))
    )
    (net (code "71") (name "/RST0") (class "Default")
      (node (ref "J2") (pin "8") (pinfunction "8_8") (pintype "passive"))
      (node (ref "U3") (pin "11") (pinfunction "PC8_11") (pintype "bidirectional"))
    )
    (net (code "72") (name "/RT") (class "Default")
      (node (ref "RT") (pin "1") (pinfunction "point_1") (pintype "passive"))
      (node (ref "U3") (pin "1") (pinfunction "RST#_1") (pintype "input"))
    )
    (net (code "73") (name "/RX_OUT") (class "Default")
      (node (ref "J2") (pin "9") (pinfunction "9_9") (pintype "passive"))
      (node (ref "R20") (pin "1") (pinfunction "1_1") (pintype "passive"))
    )
    (net (code "74") (name "/TX_OUT") (class "Default")
      (node (ref "J2") (pin "11") (pinfunction "11_11") (pintype "passive"))
      (node (ref "R34") (pin "1") (pinfunction "1_1") (pintype "passive"))
    )
    (net (code "75") (name "/UART3_RX") (class "Default")
      (node (ref "R20") (pin "2") (pinfunction "2_2") (pintype "passive"))
      (node (ref "U3") (pin "4") (pinfunction "PB11/UART3_RX/I2C2_SDA_4") (pintype "bidirectional"))
    )
    (net (code "76") (name "/UART3_TX") (class "Default")
      (node (ref "R34") (pin "2") (pinfunction "2_2") (pintype "passive"))
      (node (ref "U3") (pin "3") (pinfunction "PB10/UART3_TX/I2C2_SCL_3") (pintype "bidirectional"))
    )
    (net (code "77") (name "/USB_N") (class "Default")
      (node (ref "P9") (pin "A7") (pinfunction "D-_A7") (pintype "bidirectional"))
      (node (ref "P9") (pin "B7") (pinfunction "D-_B7") (pintype "bidirectional"))
      (node (ref "U3") (pin "16") (pinfunction "PB6/USB2DM/UART1X_TX_16") (pintype "bidirectional"))
    )
    (net (code "78") (name "/USB_P") (class "Default")
      (node (ref "P9") (pin "A6") (pinfunction "D+_A6") (pintype "bidirectional"))
      (node (ref "P9") (pin "B6") (pinfunction "D+_B6") (pintype "bidirectional"))
      (node (ref "U3") (pin "17") (pinfunction "PB7/USB2DP/UART1X_RX_17") (pintype "bidirectional"))
    )
    (net (code "79") (name "/VBAT") (class "Default")
      (node (ref "C9") (pin "1") (pinfunction "1_1") (pintype "passive"))
      (node (ref "J3") (pin "33") (pinfunction "33_33") (pintype "passive"))
      (node (ref "U2") (pin "1") (pinfunction "VBAT_1") (pintype "power_in"))
    )
    (net (code "80") (name "/VDD") (class "Default")
      (node (ref "C4") (pin "2") (pinfunction "2_2") (pintype "passive"))
      (node (ref "C7") (pin "2") (pinfunction "2_2") (pintype "passive"))
      (node (ref "R12") (pin "2") (pinfunction "2_2") (pintype "passive"))
      (node (ref "R15") (pin "2") (pinfunction "2_2") (pintype "passive"))
      (node (ref "R16") (pin "1") (pinfunction "1_1") (pintype "passive"))
      (node (ref "R7") (pin "2") (pinfunction "2_2") (pintype "passive"))
      (node (ref "U2") (pin "19") (pinfunction "VDD_4_19") (pintype "power_in"))
    )
    (net (code "81") (name "/VDDA") (class "Default")
      (node (ref "C10") (pin "1") (pinfunction "1_1") (pintype "passive"))
      (node (ref "J4") (pin "5") (pinfunction "5_5") (pintype "passive"))
      (node (ref "J7") (pin "3") (pinfunction "3_3") (pintype "passive"))
      (node (ref "R12") (pin "1") (pinfunction "1_1") (pintype "passive"))
      (node (ref "U2") (pin "13") (pinfunction "VDDA_13") (pintype "power_in"))
    )
    (net (code "82") (name "/VIO") (class "Default")
      (node (ref "C1") (pin "2") (pinfunction "2_2") (pintype "passive"))
      (node (ref "C3") (pin "2") (pinfunction "2_2") (pintype "passive"))
      (node (ref "J4") (pin "20") (pinfunction "20_20") (pintype "passive"))
      (node (ref "R15") (pin "1") (pinfunction "1_1") (pintype "passive"))
      (node (ref "U2") (pin "32") (pinfunction "VIO_1_32") (pintype "power_in"))
      (node (ref "U2") (pin "64") (pinfunction "VIO_3_64") (pintype "power_in"))
    )
    (net (code "83") (name "3V3") (class "Default")
      (node (ref "C21") (pin "1") (pinfunction "1_1") (pintype "passive"))
      (node (ref "D2") (pin "1") (pinfunction "A_1") (pintype "passive"))
      (node (ref "D3") (pin "1") (pinfunction "A_1") (pintype "passive"))
      (node (ref "J2") (pin "7") (pinfunction "7_7") (pintype "passive"))
      (node (ref "J3") (pin "1") (pinfunction "1_1") (pintype "passive"))
      (node (ref "J3") (pin "12") (pinfunction "12_12") (pintype "passive"))
      (node (ref "J3") (pin "16") (pinfunction "16_16") (pintype "passive"))
      (node (ref "J3") (pin "2") (pinfunction "2_2") (pintype "passive"))
      (node (ref "J3") (pin "3") (pinfunction "3_3") (pintype "passive"))
      (node (ref "J3") (pin "4") (pinfunction "4_4") (pintype "passive"))
      (node (ref "J5") (pin "2") (pinfunction "2_2") (pintype "passive"))
      (node (ref "J5") (pin "4") (pinfunction "4_4") (pintype "passive"))
      (node (ref "R1") (pin "2") (pinfunction "2_2") (pintype "passive"))
      (node (ref "R14") (pin "2") (pinfunction "2_2") (pintype "passive"))
      (node (ref "R2") (pin "1") (pinfunction "1_1") (pintype "passive"))
      (node (ref "R24") (pin "2") (pinfunction "2_2") (pintype "passive"))
      (node (ref "R3") (pin "1") (pinfunction "1_1") (pintype "passive"))
      (node (ref "R7") (pin "1") (pinfunction "1_1") (pintype "passive"))
      (node (ref "S3") (pin "3") (pinfunction "3_3") (pintype "passive"))
      (node (ref "U3") (pin "14") (pinfunction "VDD33/VIO_14") (pintype "power_in"))
    )
    (net (code "84") (name "5V_in") (class "Default")
      (node (ref "F2") (pin "1") (pinfunction "1_1") (pintype "passive"))
      (node (ref "P7") (pin "A4") (pinfunction "VBUS_A4") (pintype "bidirectional"))
      (node (ref "P7") (pin "B4") (pinfunction "VBUS_B4") (pintype "bidirectional"))
      (node (ref "P9") (pin "A4") (pinfunction "VBUS_A4") (pintype "bidirectional"))
      (node (ref "P9") (pin "B4") (pinfunction "VBUS_B4") (pintype "bidirectional"))
    )
    (net (code "85") (name "GND") (class "Default")
      (node (ref "C1") (pin "1") (pinfunction "1_1") (pintype "passive"))
      (node (ref "C10") (pin "2") (pinfunction "2_2") (pintype "passive"))
      (node (ref "C11") (pin "1") (pinfunction "1_1") (pintype "passive"))
      (node (ref "C12") (pin "2") (pinfunction "2_2") (pintype "passive"))
      (node (ref "C13") (pin "2") (pinfunction "2_2") (pintype "passive"))
      (node (ref "C2") (pin "1") (pinfunction "1_1") (pintype "passive"))
      (node (ref "C21") (pin "2") (pinfunction "2_2") (pintype "passive"))
      (node (ref "C3") (pin "1") (pinfunction "1_1") (pintype "passive"))
      (node (ref "C31") (pin "1") (pinfunction "1_1") (pintype "passive"))
      (node (ref "C32") (pin "1") (pinfunction "1_1") (pintype "passive"))
      (node (ref "C4") (pin "1") (pinfunction "1_1") (pintype "passive"))
      (node (ref "C5") (pin "2") (pinfunction "2_2") (pintype "passive"))
      (node (ref "C6") (pin "2") (pinfunction "2_2") (pintype "passive"))
      (node (ref "C7") (pin "1") (pinfunction "1_1") (pintype "passive"))
      (node (ref "C8") (pin "1") (pinfunction "1_1") (pintype "passive"))
      (node (ref "C9") (pin "2") (pinfunction "2_2") (pintype "passive"))
      (node (ref "J2") (pin "5") (pinfunction "5_5") (pintype "passive"))
      (node (ref "J2") (pin "6") (pinfunction "6_6") (pintype "passive"))
      (node (ref "J3") (pin "19") (pinfunction "19_19") (pintype "passive"))
      (node (ref "J3") (pin "20") (pinfunction "20_20") (pintype "passive"))
      (node (ref "J3") (pin "21") (pinfunction "21_21") (pintype "passive"))
      (node (ref "J3") (pin "22") (pinfunction "22_22") (pintype "passive"))
      (node (ref "J3") (pin "7") (pinfunction "7_7") (pintype "passive"))
      (node (ref "J3") (pin "8") (pinfunction "8_8") (pintype "passive"))
      (node (ref "J4") (pin "32") (pinfunction "32_32") (pintype "passive"))
      (node (ref "J4") (pin "7") (pinfunction "7_7") (pintype "passive"))
      (node (ref "J5") (pin "6") (pinfunction "6_6") (pintype "passive"))
      (node (ref "J5") (pin "7") (pinfunction "7_7") (pintype "passive"))
      (node (ref "J7") (pin "4") (pinfunction "4_4") (pintype "passive"))
      (node (ref "P7") (pin "A1") (pinfunction "GND_A1") (pintype "bidirectional"))
      (node (ref "P7") (pin "B1") (pinfunction "GND_B1") (pintype "bidirectional"))
      (node (ref "P9") (pin "A1") (pinfunction "GND_A1") (pintype "bidirectional"))
      (node (ref "P9") (pin "B1") (pinfunction "GND_B1") (pintype "bidirectional"))
      (node (ref "PWR") (pin "2") (pinfunction "K_2") (pintype "passive"))
      (node (ref "R10") (pin "2") (pinfunction "2_2") (pintype "passive"))
      (node (ref "R11") (pin "2") (pinfunction "2_2") (pintype "passive"))
      (node (ref "R21") (pin "1") (pinfunction "1_1") (pintype "passive"))
      (node (ref "R22") (pin "1") (pinfunction "1_1") (pintype "passive"))
      (node (ref "R8") (pin "1") (pinfunction "1_1") (pintype "passive"))
      (node (ref "R9") (pin "1") (pinfunction "1_1") (pintype "passive"))
      (node (ref "S1") (pin "3") (pinfunction "B1_3") (pintype "passive"))
      (node (ref "S2") (pin "3") (pinfunction "B1_3") (pintype "passive"))
      (node (ref "S5") (pin "2") (pinfunction "2_2") (pintype "passive"))
      (node (ref "U1") (pin "1") (pinfunction "GND_1") (pintype "passive"))
      (node (ref "U2") (pin "12") (pinfunction "VSSA_12") (pintype "power_in"))
      (node (ref "U2") (pin "18") (pinfunction "VSS_4_18") (pintype "power_in"))
      (node (ref "U2") (pin "31") (pinfunction "VSS_1_31") (pintype "power_in"))
      (node (ref "U2") (pin "63") (pinfunction "VSS_3_63") (pintype "power_in"))
      (node (ref "U3") (pin "18") (pinfunction "VSS/GND_18") (pintype "power_in"))
    )
    (net (code "86") (name "Net-(D2-K)") (class "Default")
      (node (ref "D2") (pin "2") (pinfunction "K_2") (pintype "passive"))
      (node (ref "R13") (pin "2") (pinfunction "2_2") (pintype "passive"))
    )
    (net (code "87") (name "Net-(D3-K)") (class "Default")
      (node (ref "D3") (pin "2") (pinfunction "K_2") (pintype "passive"))
      (node (ref "R21") (pin "2") (pinfunction "2_2") (pintype "passive"))
    )
    (net (code "88") (name "Net-(J3-Pad6)") (class "Default")
      (node (ref "J3") (pin "6") (pinfunction "6_6") (pintype "passive"))
      (node (ref "R5") (pin "1") (pinfunction "1_1") (pintype "passive"))
    )
    (net (code "89") (name "Net-(J3-Pad10)") (class "Default")
      (node (ref "J3") (pin "10") (pinfunction "10_10") (pintype "passive"))
      (node (ref "J5") (pin "1") (pinfunction "1_1") (pintype "passive"))
    )
    (net (code "90") (name "Net-(LED1-A)") (class "Default")
      (node (ref "LED1") (pin "1") (pinfunction "A_1") (pintype "passive"))
      (node (ref "R2") (pin "2") (pinfunction "2_2") (pintype "passive"))
    )
    (net (code "91") (name "Net-(LED2-A)") (class "Default")
      (node (ref "LED2") (pin "1") (pinfunction "A_1") (pintype "passive"))
      (node (ref "R3") (pin "2") (pinfunction "2_2") (pintype "passive"))
    )
    (net (code "92") (name "Net-(P7-CC-PadA5)") (class "Default")
      (node (ref "P7") (pin "A5") (pinfunction "CC_A5") (pintype "bidirectional"))
      (node (ref "R8") (pin "2") (pinfunction "2_2") (pintype "passive"))
    )
    (net (code "93") (name "Net-(P7-CC-PadB5)") (class "Default")
      (node (ref "P7") (pin "B5") (pinfunction "CC_B5") (pintype "bidirectional"))
      (node (ref "R9") (pin "2") (pinfunction "2_2") (pintype "passive"))
    )
    (net (code "94") (name "Net-(P9-CC-PadA5)") (class "Default")
      (node (ref "P9") (pin "A5") (pinfunction "CC_A5") (pintype "bidirectional"))
      (node (ref "R10") (pin "1") (pinfunction "1_1") (pintype "passive"))
    )
    (net (code "95") (name "Net-(P9-CC-PadB5)") (class "Default")
      (node (ref "P9") (pin "B5") (pinfunction "CC_B5") (pintype "bidirectional"))
      (node (ref "R11") (pin "1") (pinfunction "1_1") (pintype "passive"))
    )
    (net (code "96") (name "Net-(PWR-A)") (class "Default")
      (node (ref "PWR") (pin "1") (pinfunction "A_1") (pintype "passive"))
      (node (ref "R1") (pin "1") (pinfunction "1_1") (pintype "passive"))
    )
    (net (code "97") (name "Net-(U1-VOUT)") (class "Default")
      (node (ref "C13") (pin "1") (pinfunction "1_1") (pintype "passive"))
      (node (ref "S3") (pin "1") (pinfunction "1_1") (pintype "passive"))
      (node (ref "U1") (pin "2") (pinfunction "VOUT_2") (pintype "passive"))
    )
    (net (code "98") (name "Net-(U2-VDD_2)") (class "Default")
      (node (ref "R16") (pin "2") (pinfunction "2_2") (pintype "passive"))
      (node (ref "U2") (pin "48") (pinfunction "VDD_2_48") (pintype "power_in"))
    )
    (net (code "99") (name "Net-(U2-VSS_2)") (class "Default")
      (node (ref "R22") (pin "2") (pinfunction "2_2") (pintype "passive"))
      (node (ref "U2") (pin "47") (pinfunction "VSS_2_47") (pintype "power_in"))
    )
    (net (code "100") (name "unconnected-(P7-RFU1-PadA8)") (class "Default")
      (node (ref "P7") (pin "A8") (pinfunction "RFU1_A8") (pintype "bidirectional+no_connect"))
    )
    (net (code "101") (name "unconnected-(P7-RFU1-PadB8)") (class "Default")
      (node (ref "P7") (pin "B8") (pinfunction "RFU1_B8") (pintype "bidirectional+no_connect"))
    )
    (net (code "102") (name "unconnected-(P9-RFU1-PadA8)") (class "Default")
      (node (ref "P9") (pin "A8") (pinfunction "RFU1_A8") (pintype "bidirectional+no_connect"))
    )
    (net (code "103") (name "unconnected-(P9-RFU1-PadB8)") (class "Default")
      (node (ref "P9") (pin "B8") (pinfunction "RFU1_B8") (pintype "bidirectional+no_connect"))
    )
    (net (code "104") (name "unconnected-(S1-A1-Pad4)") (class "Default")
      (node (ref "S1") (pin "4") (pinfunction "A1_4") (pintype "passive"))
    )
    (net (code "105") (name "unconnected-(S1-B0-Pad2)") (class "Default")
      (node (ref "S1") (pin "2") (pinfunction "B0_2") (pintype "passive"))
    )
    (net (code "106") (name "unconnected-(S2-A1-Pad4)") (class "Default")
      (node (ref "S2") (pin "4") (pinfunction "A1_4") (pintype "passive"))
    )
    (net (code "107") (name "unconnected-(S2-B0-Pad2)") (class "Default")
      (node (ref "S2") (pin "2") (pinfunction "B0_2") (pintype "passive"))
    )
    (net (code "108") (name "unconnected-(S3-Pad2)") (class "Default")
      (node (ref "S3") (pin "2") (pinfunction "2_2") (pintype "passive"))
    )
    (net (code "109") (name "unconnected-(U3-PA5{slash}UART1_CTS{slash}PA1_(no5V)-Pad2)") (class "Default")
      (node (ref "U3") (pin "2") (pinfunction "PA5/UART1_CTS/PA1_(no5V)_2") (pintype "bidirectional+no_connect"))
    )
    (net (code "110") (name "unconnected-(U3-PB12{slash}SPI2_NSS{slash}CAN2_RX-Pad5)") (class "Default")
      (node (ref "U3") (pin "5") (pinfunction "PB12/SPI2_NSS/CAN2_RX_5") (pintype "bidirectional+no_connect"))
    )
    (net (code "111") (name "unconnected-(U3-PB14{slash}SPI2_MISO{slash}UART3_RTS-Pad7)") (class "Default")
      (node (ref "U3") (pin "7") (pinfunction "PB14/SPI2_MISO/UART3_RTS_7") (pintype "bidirectional+no_connect"))
    )
    (net (code "112") (name "unconnected-(U3-PB15{slash}SPI2_MOSI{slash}UART1_TX-Pad8)") (class "Default")
      (node (ref "U3") (pin "8") (pinfunction "PB15/SPI2_MOSI/UART1_TX_8") (pintype "bidirectional+no_connect"))
    )
  )
)
